# rev2.net
KiCad netlist of a schematic drawn in EAGLE
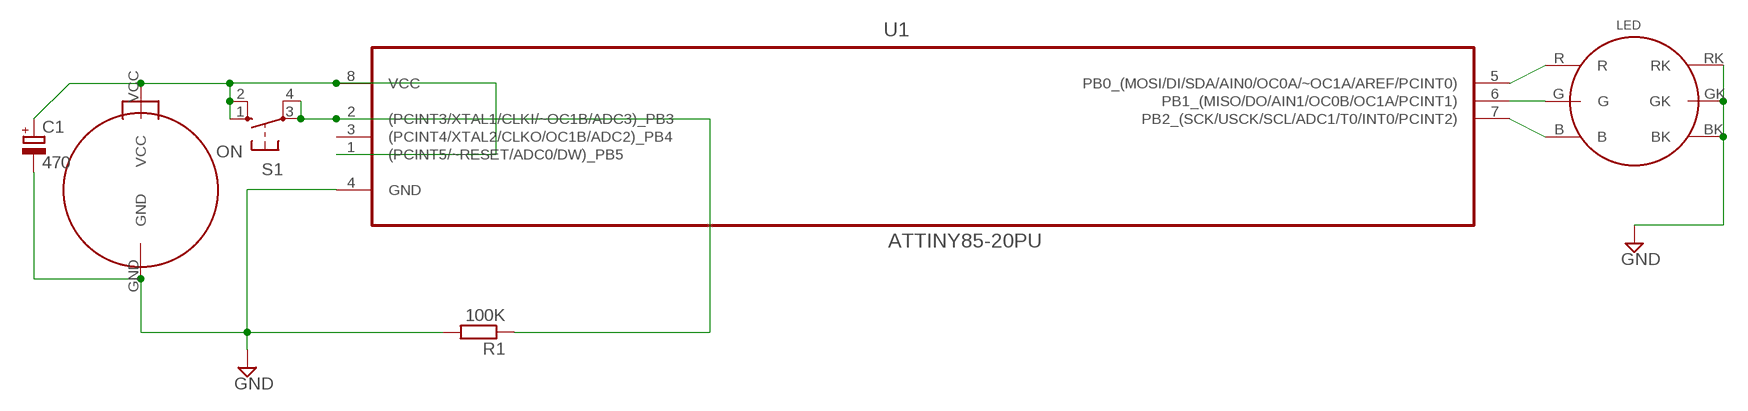
[diagram p0: schematic, sheet 1]

(export (version "E")
  (design (tool "Eeschema 10.0.6"))
  (components
    (comp (ref "C1")
      (value "470")
      (footprint "eagle-import:E2,5-6")
      (libsource (lib "eagle-import") (part "CPOL-EUE2.5-6"))
    )
    (comp (ref "LED")
      (value "3WLED")
      (footprint "eagle-import:3WRGB")
      (libsource (lib "eagle-import") (part "3WLED"))
    )
    (comp (ref "R1")
      (value "100K")
      (footprint "eagle-import:0207_10")
      (libsource (lib "eagle-import") (part "R-EU_0207/10"))
    )
    (comp (ref "S1")
      (value "ON")
      (footprint "eagle-import:B3F-10XX")
      (fields (field (name "MPN") "B3F-1000"))
      (libsource (lib "eagle-import") (part "10-XX"))
    )
    (comp (ref "U$1")
      (value "CR2032_2PIN")
      (footprint "eagle-import:CR2032_2PIN")
      (libsource (lib "eagle-import") (part "CR2032_2PIN"))
    )
    (comp (ref "U1")
      (value "ATTINY85-20PU")
      (footprint "eagle-import:DIP254P762X533-8")
      (libsource (lib "eagle-import") (part "ATTINY85-20PU"))
    )
  )
  (nets
    (net (code "1") (name "GND") (class "Default")
      (node (ref "C1") (pin "-") (pinfunction "-_-") (pintype "passive"))
      (node (ref "LED") (pin "BK") (pinfunction "BK_BK") (pintype "bidirectional"))
      (node (ref "LED") (pin "GK") (pinfunction "GK_GK") (pintype "bidirectional"))
      (node (ref "LED") (pin "RK") (pinfunction "RK_RK") (pintype "bidirectional"))
      (node (ref "R1") (pin "2") (pinfunction "2_2") (pintype "passive"))
      (node (ref "U$1") (pin "GND") (pinfunction "GND_GND") (pintype "bidirectional"))
      (node (ref "U1") (pin "4") (pinfunction "GND_4") (pintype "passive"))
    )
    (net (code "2") (name "Net-(S1-P)") (class "Default")
      (node (ref "R1") (pin "1") (pinfunction "1_1") (pintype "passive"))
      (node (ref "S1") (pin "3") (pinfunction "P_3") (pintype "passive"))
      (node (ref "S1") (pin "4") (pinfunction "P1_4") (pintype "passive"))
      (node (ref "U1") (pin "2") (pinfunction "(PCINT3/XTAL1/CLKI/~{OC1B/ADC3})_PB3_2") (pintype "bidirectional"))
    )
    (net (code "3") (name "Net-(S1-S)") (class "Default")
      (node (ref "C1") (pin "+") (pinfunction "+_+") (pintype "passive"))
      (node (ref "S1") (pin "1") (pinfunction "S_1") (pintype "passive"))
      (node (ref "S1") (pin "2") (pinfunction "S1_2") (pintype "passive"))
      (node (ref "U$1") (pin "VCC") (pinfunction "VCC_VCC") (pintype "bidirectional"))
      (node (ref "U1") (pin "1") (pinfunction "(PCINT5/~{RESET/ADC0/DW})_PB5_1") (pintype "bidirectional"))
      (node (ref "U1") (pin "8") (pinfunction "VCC_8") (pintype "power_in"))
    )
    (net (code "4") (name "Net-(U1-PB0_(MOSI{slash}DI{slash}SDA{slash}AIN0{slash}OC0A{slash}~{OC1A{slash}AREF{slash}PCINT0}))") (class "Default")
      (node (ref "LED") (pin "R") (pinfunction "R_R") (pintype "bidirectional"))
      (node (ref "U1") (pin "5") (pinfunction "PB0_(MOSI/DI/SDA/AIN0/OC0A/~{OC1A/AREF/PCINT0})_5") (pintype "bidirectional"))
    )
    (net (code "5") (name "Net-(U1-PB1_(MISO{slash}DO{slash}AIN1{slash}OC0B{slash}OC1A{slash}PCINT1))") (class "Default")
      (node (ref "LED") (pin "G") (pinfunction "G_G") (pintype "bidirectional"))
      (node (ref "U1") (pin "6") (pinfunction "PB1_(MISO/DO/AIN1/OC0B/OC1A/PCINT1)_6") (pintype "bidirectional"))
    )
    (net (code "6") (name "Net-(U1-PB2_(SCK{slash}USCK{slash}SCL{slash}ADC1{slash}T0{slash}INT0{slash}PCINT2))") (class "Default")
      (node (ref "LED") (pin "B") (pinfunction "B_B") (pintype "bidirectional"))
      (node (ref "U1") (pin "7") (pinfunction "PB2_(SCK/USCK/SCL/ADC1/T0/INT0/PCINT2)_7") (pintype "bidirectional"))
    )
    (net (code "7") (name "unconnected-(U1-(PCINT4{slash}XTAL2{slash}CLKO{slash}OC1B{slash}ADC2)_PB4-Pad3)") (class "Default")
      (node (ref "U1") (pin "3") (pinfunction "(PCINT4/XTAL2/CLKO/OC1B/ADC2)_PB4_3") (pintype "bidirectional"))
    )
  )
)
